# USBGpib.net
KiCad netlist of a schematic drawn in EAGLE
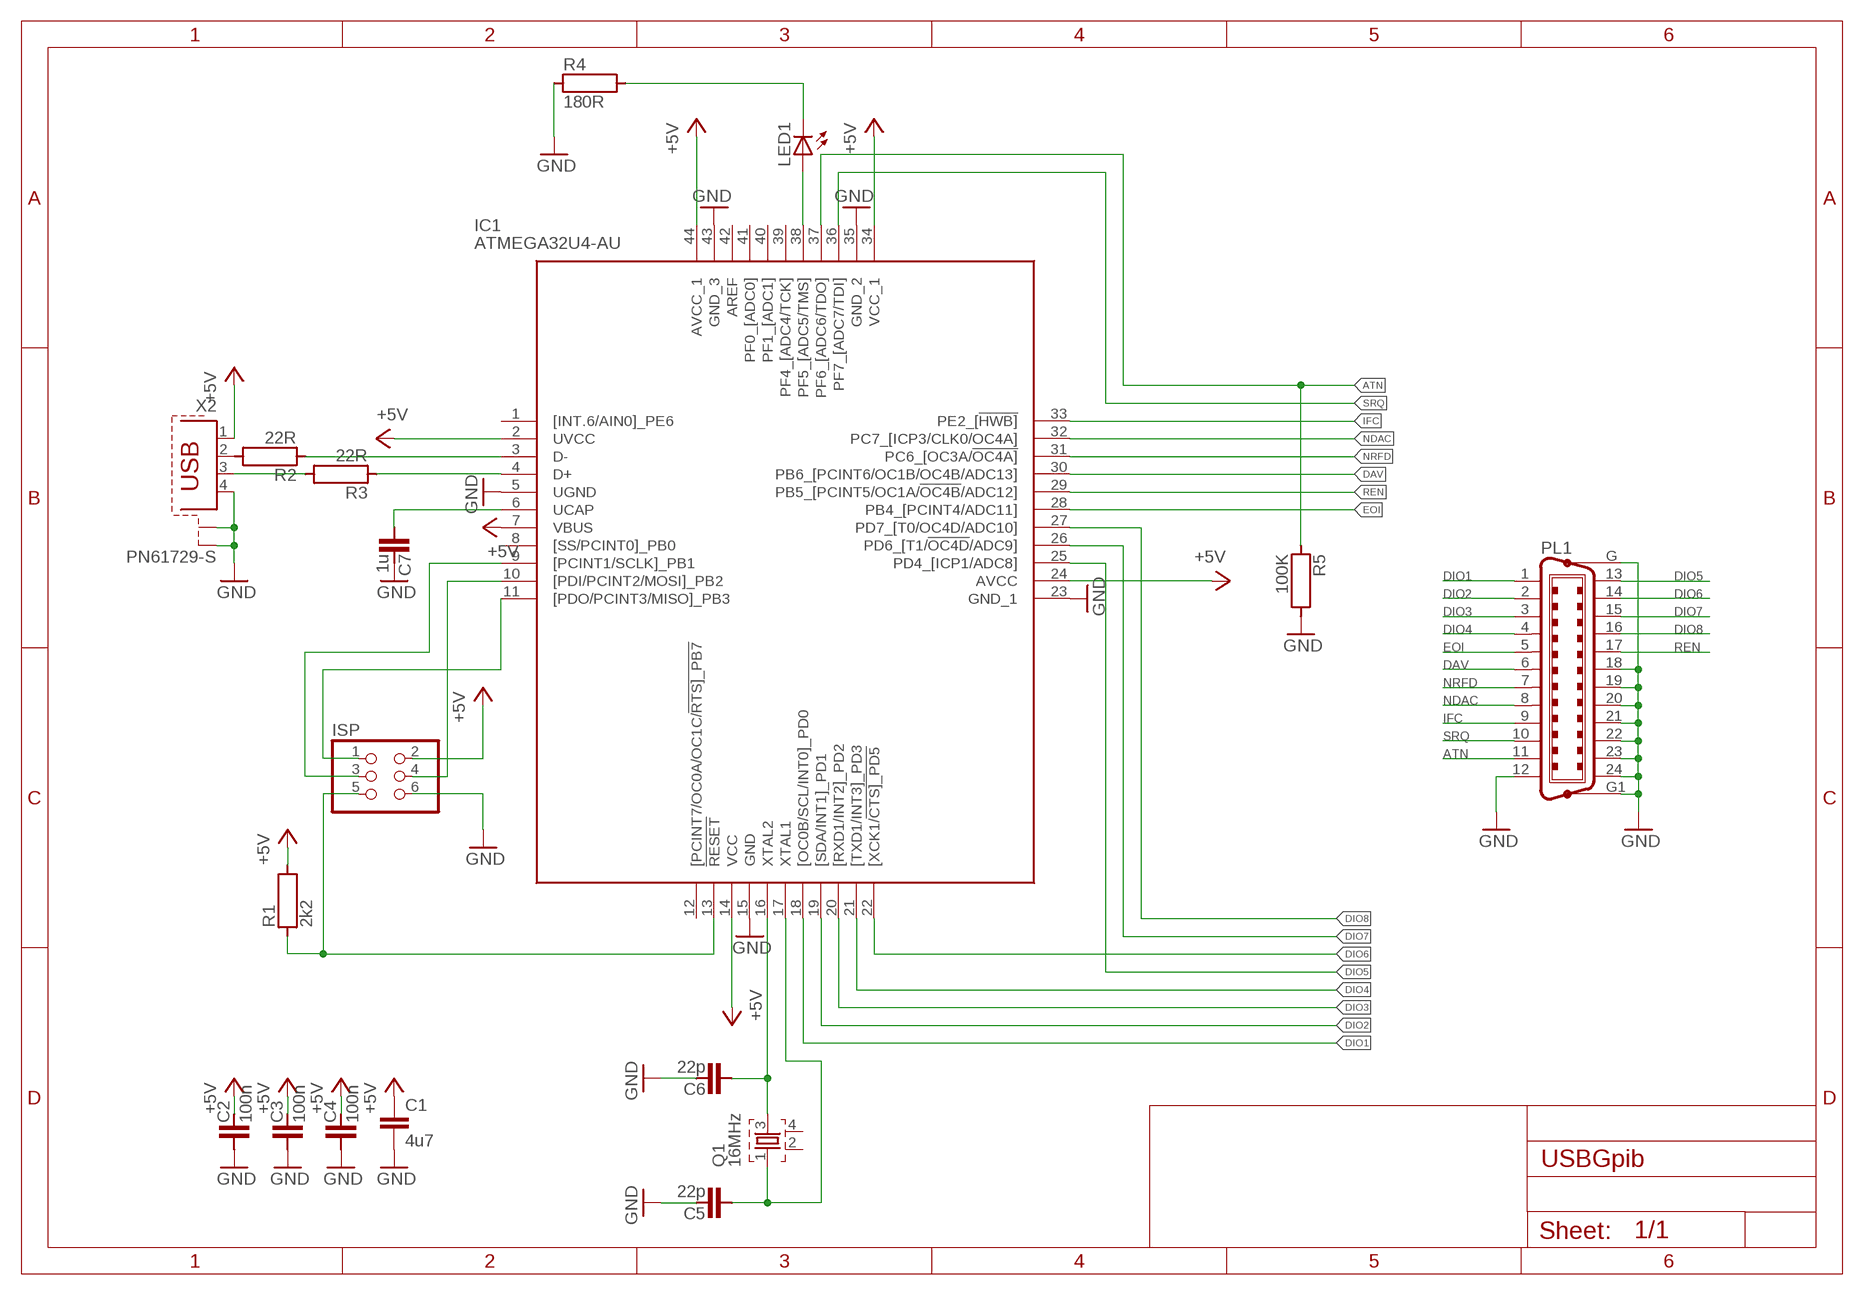
[diagram p0: schematic, sheet 1]

(export (version "E")
  (design (tool "Eeschema 10.0.6"))
  (components
    (comp (ref "C1")
      (value "4u7")
      (footprint "eagle-import:C1210")
      (libsource (lib "eagle-import") (part "C-EUC1210"))
    )
    (comp (ref "C2")
      (value "100n")
      (footprint "eagle-import:C0402")
      (libsource (lib "eagle-import") (part "C0402"))
    )
    (comp (ref "C3")
      (value "100n")
      (footprint "eagle-import:C0402")
      (libsource (lib "eagle-import") (part "C0402"))
    )
    (comp (ref "C4")
      (value "100n")
      (footprint "eagle-import:C0402")
      (libsource (lib "eagle-import") (part "C0402"))
    )
    (comp (ref "C5")
      (value "22p")
      (footprint "eagle-import:C0402")
      (libsource (lib "eagle-import") (part "C0402"))
    )
    (comp (ref "C6")
      (value "22p")
      (footprint "eagle-import:C0402")
      (libsource (lib "eagle-import") (part "C0402"))
    )
    (comp (ref "C7")
      (value "1u")
      (footprint "eagle-import:C0603")
      (libsource (lib "eagle-import") (part "C0603"))
    )
    (comp (ref "IC1")
      (value "ATMEGA32U4-AU")
      (footprint "eagle-import:QFP80P1200X1200X120-44N")
      (fields
        (field (name "MANUFACTURER_PART_NUMBER") "ATMEGA16U4-AU")
        (field (name "MOUSER_PART_NUMBER") "556-ATMEGA16U4-AU")
        (field (name "RS_PART_NUMBER") "1773649P")
      )
      (libsource (lib "eagle-import") (part "ATMEGA16U4-AU"))
    )
    (comp (ref "ISP")
      (value "PINHD-2X3")
      (footprint "eagle-import:2X03")
      (libsource (lib "eagle-import") (part "PINHD-2X3"))
    )
    (comp (ref "LED1")
      (value "LEDCHIPLED_1206")
      (footprint "eagle-import:CHIPLED_1206")
      (libsource (lib "eagle-import") (part "LEDCHIPLED_1206"))
    )
    (comp (ref "PL1")
      (value "C24HPMALE")
      (footprint "eagle-import:24HP_MALE")
      (libsource (lib "eagle-import") (part "C24HPMALE"))
    )
    (comp (ref "Q1")
      (value "16MHz")
      (footprint "eagle-import:FA-20H")
      (libsource (lib "eagle-import") (part "FA-20H"))
    )
    (comp (ref "R1")
      (value "2k2")
      (footprint "eagle-import:R0402")
      (libsource (lib "eagle-import") (part "R0402"))
    )
    (comp (ref "R2")
      (value "22R")
      (footprint "eagle-import:R0402")
      (libsource (lib "eagle-import") (part "R0402"))
    )
    (comp (ref "R3")
      (value "22R")
      (footprint "eagle-import:R0402")
      (libsource (lib "eagle-import") (part "R0402"))
    )
    (comp (ref "R4")
      (value "180R")
      (footprint "eagle-import:R0402")
      (libsource (lib "eagle-import") (part "R0402"))
    )
    (comp (ref "R5")
      (value "100K")
      (footprint "eagle-import:R0402")
      (libsource (lib "eagle-import") (part "R0402"))
    )
    (comp (ref "X2")
      (value "PN61729-S")
      (footprint "eagle-import:PN61729-S")
      (libsource (lib "eagle-import") (part "PN61729-S"))
    )
  )
  (nets
    (net (code "1") (name "+5V") (class "Default")
      (node (ref "C1") (pin "1") (pinfunction "1_1") (pintype "passive"))
      (node (ref "C2") (pin "2") (pinfunction "2_2") (pintype "passive"))
      (node (ref "C3") (pin "2") (pinfunction "2_2") (pintype "passive"))
      (node (ref "C4") (pin "2") (pinfunction "2_2") (pintype "passive"))
      (node (ref "IC1") (pin "14") (pinfunction "VCC_14") (pintype "power_in"))
      (node (ref "IC1") (pin "2") (pinfunction "UVCC_2") (pintype "power_in"))
      (node (ref "IC1") (pin "24") (pinfunction "AVCC_24") (pintype "power_in"))
      (node (ref "IC1") (pin "34") (pinfunction "VCC_1_34") (pintype "power_in"))
      (node (ref "IC1") (pin "44") (pinfunction "AVCC_1_44") (pintype "power_in"))
      (node (ref "IC1") (pin "7") (pinfunction "VBUS_7") (pintype "bidirectional"))
      (node (ref "ISP") (pin "2") (pinfunction "2_2") (pintype "passive"))
      (node (ref "R1") (pin "2") (pinfunction "2_2") (pintype "passive"))
      (node (ref "X2") (pin "1") (pinfunction "1_1") (pintype "passive"))
    )
    (net (code "2") (name "ATN") (class "Default")
      (node (ref "IC1") (pin "37") (pinfunction "PF6_[ADC6/TDO]_37") (pintype "bidirectional"))
      (node (ref "PL1") (pin "11") (pinfunction "11_11") (pintype "passive"))
      (node (ref "R5") (pin "1") (pinfunction "1_1") (pintype "passive"))
    )
    (net (code "3") (name "DAV") (class "Default")
      (node (ref "IC1") (pin "30") (pinfunction "PB6_[PCINT6/OC1B/OC4B/ADC13]_30") (pintype "input"))
      (node (ref "PL1") (pin "6") (pinfunction "6_6") (pintype "passive"))
    )
    (net (code "4") (name "DIO1") (class "Default")
      (node (ref "IC1") (pin "18") (pinfunction "[OC0B/SCL/INT0]_PD0_18") (pintype "input"))
      (node (ref "PL1") (pin "1") (pinfunction "1_1") (pintype "passive"))
    )
    (net (code "5") (name "DIO2") (class "Default")
      (node (ref "IC1") (pin "19") (pinfunction "[SDA/INT1]_PD1_19") (pintype "input"))
      (node (ref "PL1") (pin "2") (pinfunction "2_2") (pintype "passive"))
    )
    (net (code "6") (name "DIO3") (class "Default")
      (node (ref "IC1") (pin "20") (pinfunction "[RXD1/INT2]_PD2_20") (pintype "input"))
      (node (ref "PL1") (pin "3") (pinfunction "3_3") (pintype "passive"))
    )
    (net (code "7") (name "DIO4") (class "Default")
      (node (ref "IC1") (pin "21") (pinfunction "[TXD1/INT3]_PD3_21") (pintype "input"))
      (node (ref "PL1") (pin "4") (pinfunction "4_4") (pintype "passive"))
    )
    (net (code "8") (name "DIO5") (class "Default")
      (node (ref "IC1") (pin "25") (pinfunction "PD4_[ICP1/ADC8]_25") (pintype "bidirectional"))
      (node (ref "PL1") (pin "13") (pinfunction "13_13") (pintype "passive"))
    )
    (net (code "9") (name "DIO6") (class "Default")
      (node (ref "IC1") (pin "22") (pinfunction "[XCK1/~{CTS]_PD5}_22") (pintype "bidirectional"))
      (node (ref "PL1") (pin "14") (pinfunction "14_14") (pintype "passive"))
    )
    (net (code "10") (name "DIO7") (class "Default")
      (node (ref "IC1") (pin "26") (pinfunction "PD6_[T1/~{OC4D}/ADC9]_26") (pintype "bidirectional"))
      (node (ref "PL1") (pin "15") (pinfunction "15_15") (pintype "passive"))
    )
    (net (code "11") (name "DIO8") (class "Default")
      (node (ref "IC1") (pin "27") (pinfunction "PD7_[T0/OC4D/ADC10]_27") (pintype "bidirectional"))
      (node (ref "PL1") (pin "16") (pinfunction "16_16") (pintype "passive"))
    )
    (net (code "12") (name "EOI") (class "Default")
      (node (ref "IC1") (pin "28") (pinfunction "PB4_[PCINT4/ADC11]_28") (pintype "input"))
      (node (ref "PL1") (pin "5") (pinfunction "5_5") (pintype "passive"))
    )
    (net (code "13") (name "GND") (class "Default")
      (node (ref "C1") (pin "2") (pinfunction "2_2") (pintype "passive"))
      (node (ref "C2") (pin "1") (pinfunction "1_1") (pintype "passive"))
      (node (ref "C3") (pin "1") (pinfunction "1_1") (pintype "passive"))
      (node (ref "C4") (pin "1") (pinfunction "1_1") (pintype "passive"))
      (node (ref "C5") (pin "2") (pinfunction "2_2") (pintype "passive"))
      (node (ref "C6") (pin "2") (pinfunction "2_2") (pintype "passive"))
      (node (ref "C7") (pin "2") (pinfunction "2_2") (pintype "passive"))
      (node (ref "IC1") (pin "15") (pinfunction "GND_15") (pintype "power_in"))
      (node (ref "IC1") (pin "23") (pinfunction "GND_1_23") (pintype "power_in"))
      (node (ref "IC1") (pin "35") (pinfunction "GND_2_35") (pintype "power_in"))
      (node (ref "IC1") (pin "43") (pinfunction "GND_3_43") (pintype "power_in"))
      (node (ref "IC1") (pin "5") (pinfunction "UGND_5") (pintype "power_in"))
      (node (ref "ISP") (pin "6") (pinfunction "6_6") (pintype "passive"))
      (node (ref "PL1") (pin "12") (pinfunction "12_12") (pintype "passive"))
      (node (ref "PL1") (pin "18") (pinfunction "18_18") (pintype "passive"))
      (node (ref "PL1") (pin "19") (pinfunction "19_19") (pintype "passive"))
      (node (ref "PL1") (pin "20") (pinfunction "20_20") (pintype "passive"))
      (node (ref "PL1") (pin "21") (pinfunction "21_21") (pintype "passive"))
      (node (ref "PL1") (pin "22") (pinfunction "22_22") (pintype "passive"))
      (node (ref "PL1") (pin "23") (pinfunction "23_23") (pintype "passive"))
      (node (ref "PL1") (pin "24") (pinfunction "24_24") (pintype "passive"))
      (node (ref "PL1") (pin "G") (pinfunction "G_G") (pintype "passive"))
      (node (ref "PL1") (pin "G1") (pinfunction "G1_G1") (pintype "passive"))
      (node (ref "R4") (pin "1") (pinfunction "1_1") (pintype "passive"))
      (node (ref "R5") (pin "2") (pinfunction "2_2") (pintype "passive"))
      (node (ref "X2") (pin "4") (pinfunction "4_4") (pintype "passive"))
      (node (ref "X2") (pin "S1") (pinfunction "S1_S1") (pintype "passive"))
      (node (ref "X2") (pin "S2") (pinfunction "S2_S2") (pintype "passive"))
    )
    (net (code "14") (name "IFC") (class "Default")
      (node (ref "IC1") (pin "33") (pinfunction "PE2_[~{HWB]}_33") (pintype "bidirectional"))
      (node (ref "PL1") (pin "9") (pinfunction "9_9") (pintype "passive"))
    )
    (net (code "15") (name "NDAC") (class "Default")
      (node (ref "IC1") (pin "32") (pinfunction "PC7_[ICP3/CLK0/OC4A]_32") (pintype "input"))
      (node (ref "PL1") (pin "8") (pinfunction "8_8") (pintype "passive"))
    )
    (net (code "16") (name "NRFD") (class "Default")
      (node (ref "IC1") (pin "31") (pinfunction "PC6_[OC3A/~{OC4A]}_31") (pintype "bidirectional"))
      (node (ref "PL1") (pin "7") (pinfunction "7_7") (pintype "passive"))
    )
    (net (code "17") (name "Net-(IC1-D+)") (class "Default")
      (node (ref "IC1") (pin "4") (pinfunction "D+_4") (pintype "bidirectional"))
      (node (ref "R3") (pin "1") (pinfunction "1_1") (pintype "passive"))
    )
    (net (code "18") (name "Net-(IC1-D-)") (class "Default")
      (node (ref "IC1") (pin "3") (pinfunction "D-_3") (pintype "bidirectional"))
      (node (ref "R2") (pin "1") (pinfunction "1_1") (pintype "passive"))
    )
    (net (code "19") (name "Net-(IC1-PF5_[ADC5{slash}TMS])") (class "Default")
      (node (ref "IC1") (pin "38") (pinfunction "PF5_[ADC5/TMS]_38") (pintype "bidirectional"))
      (node (ref "LED1") (pin "A") (pinfunction "A_A") (pintype "passive"))
    )
    (net (code "20") (name "Net-(IC1-UCAP)") (class "Default")
      (node (ref "C7") (pin "1") (pinfunction "1_1") (pintype "passive"))
      (node (ref "IC1") (pin "6") (pinfunction "UCAP_6") (pintype "bidirectional"))
    )
    (net (code "21") (name "Net-(IC1-XTAL1)") (class "Default")
      (node (ref "C5") (pin "1") (pinfunction "1_1") (pintype "passive"))
      (node (ref "IC1") (pin "17") (pinfunction "XTAL1_17") (pintype "bidirectional"))
      (node (ref "Q1") (pin "1") (pinfunction "1_1") (pintype "passive"))
    )
    (net (code "22") (name "Net-(IC1-XTAL2)") (class "Default")
      (node (ref "C6") (pin "1") (pinfunction "1_1") (pintype "passive"))
      (node (ref "IC1") (pin "16") (pinfunction "XTAL2_16") (pintype "bidirectional"))
      (node (ref "Q1") (pin "3") (pinfunction "3_3") (pintype "passive"))
    )
    (net (code "23") (name "Net-(IC1-[PCINT1{slash}SCLK]_PB1)") (class "Default")
      (node (ref "IC1") (pin "9") (pinfunction "[PCINT1/SCLK]_PB1_9") (pintype "input"))
      (node (ref "ISP") (pin "3") (pinfunction "3_3") (pintype "passive"))
    )
    (net (code "24") (name "Net-(IC1-[PDI{slash}PCINT2{slash}MOSI]_PB2)") (class "Default")
      (node (ref "IC1") (pin "10") (pinfunction "[PDI/PCINT2/MOSI]_PB2_10") (pintype "input"))
      (node (ref "ISP") (pin "4") (pinfunction "4_4") (pintype "passive"))
    )
    (net (code "25") (name "Net-(IC1-[PDO{slash}PCINT3{slash}MISO]_PB3)") (class "Default")
      (node (ref "IC1") (pin "11") (pinfunction "[PDO/PCINT3/MISO]_PB3_11") (pintype "input"))
      (node (ref "ISP") (pin "1") (pinfunction "1_1") (pintype "passive"))
    )
    (net (code "26") (name "Net-(IC1-~{RESET})") (class "Default")
      (node (ref "IC1") (pin "13") (pinfunction "~{RESET}_13") (pintype "bidirectional"))
      (node (ref "ISP") (pin "5") (pinfunction "5_5") (pintype "passive"))
      (node (ref "R1") (pin "1") (pinfunction "1_1") (pintype "passive"))
    )
    (net (code "27") (name "Net-(LED1-PadC)") (class "Default")
      (node (ref "LED1") (pin "C") (pinfunction "C_C") (pintype "passive"))
      (node (ref "R4") (pin "2") (pinfunction "2_2") (pintype "passive"))
    )
    (net (code "28") (name "Net-(R2-Pad2)") (class "Default")
      (node (ref "R2") (pin "2") (pinfunction "2_2") (pintype "passive"))
      (node (ref "X2") (pin "2") (pinfunction "2_2") (pintype "passive"))
    )
    (net (code "29") (name "Net-(R3-Pad2)") (class "Default")
      (node (ref "R3") (pin "2") (pinfunction "2_2") (pintype "passive"))
      (node (ref "X2") (pin "3") (pinfunction "3_3") (pintype "passive"))
    )
    (net (code "30") (name "REN") (class "Default")
      (node (ref "IC1") (pin "29") (pinfunction "PB5_[PCINT5/OC1A/~{OC4B}/ADC12]_29") (pintype "input"))
      (node (ref "PL1") (pin "17") (pinfunction "17_17") (pintype "passive"))
    )
    (net (code "31") (name "SRQ") (class "Default")
      (node (ref "IC1") (pin "36") (pinfunction "PF7_[ADC7/TDI]_36") (pintype "bidirectional"))
      (node (ref "PL1") (pin "10") (pinfunction "10_10") (pintype "passive"))
    )
    (net (code "32") (name "unconnected-(IC1-AREF-Pad42)") (class "Default")
      (node (ref "IC1") (pin "42") (pinfunction "AREF_42") (pintype "input"))
    )
    (net (code "33") (name "unconnected-(IC1-PF0_[ADC0]-Pad41)") (class "Default")
      (node (ref "IC1") (pin "41") (pinfunction "PF0_[ADC0]_41") (pintype "bidirectional"))
    )
    (net (code "34") (name "unconnected-(IC1-PF1_[ADC1]-Pad40)") (class "Default")
      (node (ref "IC1") (pin "40") (pinfunction "PF1_[ADC1]_40") (pintype "bidirectional"))
    )
    (net (code "35") (name "unconnected-(IC1-PF4_[ADC4{slash}TCK]-Pad39)") (class "Default")
      (node (ref "IC1") (pin "39") (pinfunction "PF4_[ADC4/TCK]_39") (pintype "bidirectional"))
    )
    (net (code "36") (name "unconnected-(IC1-[INT.6{slash}AIN0]_PE6-Pad1)") (class "Default")
      (node (ref "IC1") (pin "1") (pinfunction "[INT.6/AIN0]_PE6_1") (pintype "input"))
    )
    (net (code "37") (name "unconnected-(IC1-[PCINT7{slash}OC0A{slash}OC1C{slash}~{RTS]_PB7}-Pad12)") (class "Default")
      (node (ref "IC1") (pin "12") (pinfunction "[PCINT7/OC0A/OC1C/~{RTS]_PB7}_12") (pintype "input"))
    )
    (net (code "38") (name "unconnected-(IC1-[SS{slash}PCINT0]_PB0-Pad8)") (class "Default")
      (node (ref "IC1") (pin "8") (pinfunction "[SS/PCINT0]_PB0_8") (pintype "input"))
    )
    (net (code "39") (name "unconnected-(Q1-Pad2)") (class "Default")
      (node (ref "Q1") (pin "2") (pinfunction "2_2") (pintype "passive"))
    )
    (net (code "40") (name "unconnected-(Q1-Pad4)") (class "Default")
      (node (ref "Q1") (pin "4") (pinfunction "4_4") (pintype "passive"))
    )
  )
)
